# ControlModule.net
KiCad netlist of a schematic drawn in EAGLE
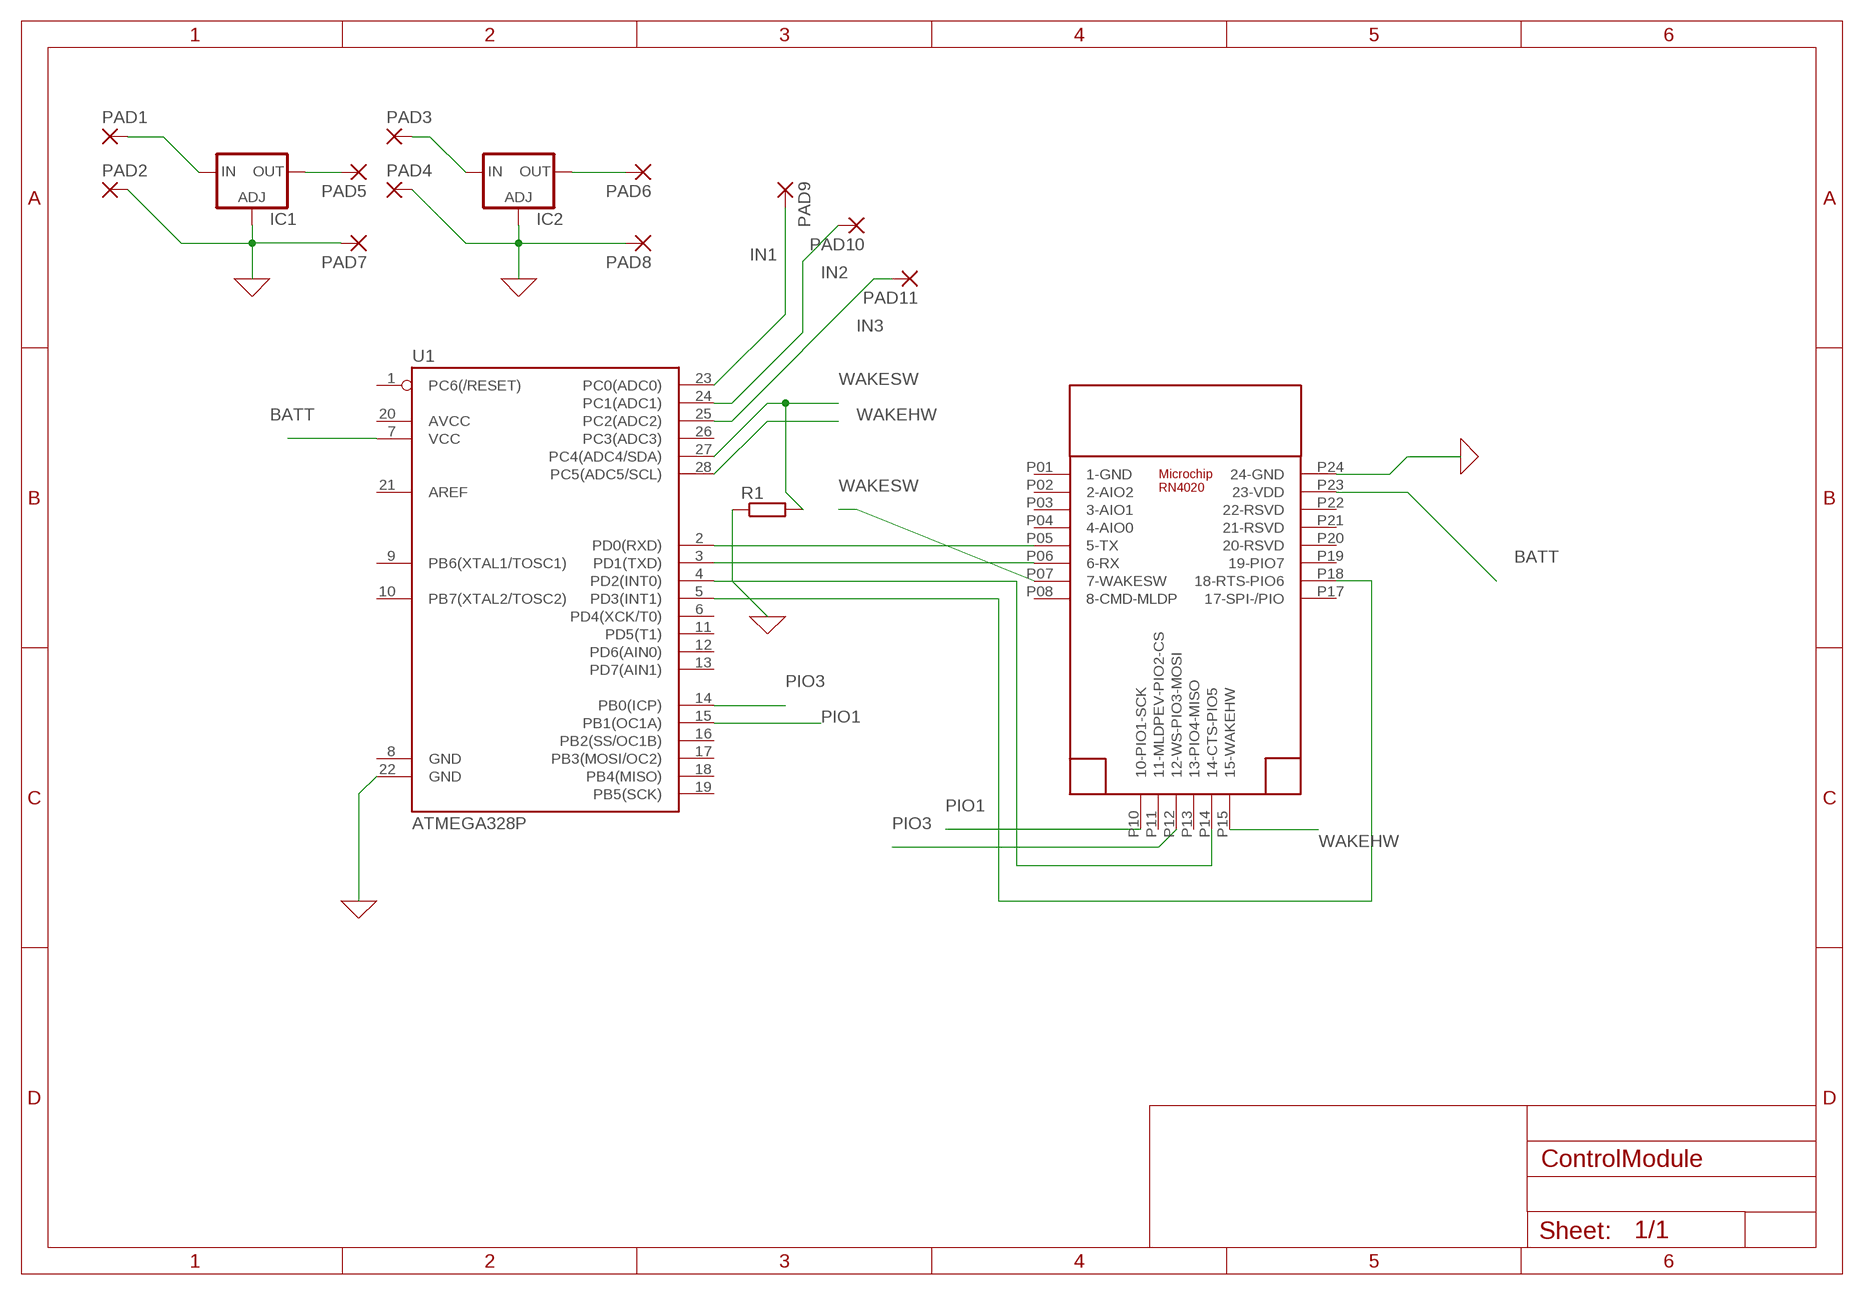
[diagram p0: schematic, sheet 1]

(export (version "E")
  (design (tool "Eeschema 10.0.6"))
  (components
    (comp (ref "IC1")
      (value "LM138-TL")
      (footprint "eagle-import:TO220L1")
      (libsource (lib "eagle-import") (part "LM138-TL"))
    )
    (comp (ref "IC2")
      (value "LM138-TL")
      (footprint "eagle-import:TO220L1")
      (libsource (lib "eagle-import") (part "LM138-TL"))
    )
    (comp (ref "PAD1")
      (value "2,54/1,1")
      (footprint "eagle-import:2,54_1,1")
      (libsource (lib "eagle-import") (part "2,54/1,1"))
    )
    (comp (ref "PAD2")
      (value "2,54/1,1")
      (footprint "eagle-import:2,54_1,1")
      (libsource (lib "eagle-import") (part "2,54/1,1"))
    )
    (comp (ref "PAD3")
      (value "2,54/1,1")
      (footprint "eagle-import:2,54_1,1")
      (libsource (lib "eagle-import") (part "2,54/1,1"))
    )
    (comp (ref "PAD4")
      (value "2,54/1,1")
      (footprint "eagle-import:2,54_1,1")
      (libsource (lib "eagle-import") (part "2,54/1,1"))
    )
    (comp (ref "PAD5")
      (value "2,54/1,1")
      (footprint "eagle-import:2,54_1,1")
      (libsource (lib "eagle-import") (part "2,54/1,1"))
    )
    (comp (ref "PAD6")
      (value "2,54/1,1")
      (footprint "eagle-import:2,54_1,1")
      (libsource (lib "eagle-import") (part "2,54/1,1"))
    )
    (comp (ref "PAD7")
      (value "2,54/1,1")
      (footprint "eagle-import:2,54_1,1")
      (libsource (lib "eagle-import") (part "2,54/1,1"))
    )
    (comp (ref "PAD8")
      (value "2,54/1,1")
      (footprint "eagle-import:2,54_1,1")
      (libsource (lib "eagle-import") (part "2,54/1,1"))
    )
    (comp (ref "PAD9")
      (value "2,54/1,1")
      (footprint "eagle-import:2,54_1,1")
      (libsource (lib "eagle-import") (part "2,54/1,1"))
    )
    (comp (ref "PAD10")
      (value "2,54/1,1")
      (footprint "eagle-import:2,54_1,1")
      (libsource (lib "eagle-import") (part "2,54/1,1"))
    )
    (comp (ref "PAD11")
      (value "2,54/1,1")
      (footprint "eagle-import:2,54_1,1")
      (libsource (lib "eagle-import") (part "2,54/1,1"))
    )
    (comp (ref "R1")
      (value "R-EU_R0805")
      (footprint "eagle-import:R0805")
      (libsource (lib "eagle-import") (part "R-EU_R0805"))
    )
    (comp (ref "U$1")
      (value "RN4020")
      (footprint "eagle-import:RN4020SMD")
      (libsource (lib "eagle-import") (part "RN4020"))
    )
    (comp (ref "U1")
      (value "ATMEGA328P")
      (footprint "eagle-import:DIP28")
      (libsource (lib "eagle-import") (part "ATMEGA328P_PDIP"))
    )
  )
  (nets
    (net (code "1") (name "/BATT") (class "Default")
      (node (ref "U$1") (pin "P23") (pinfunction "23-VDD_P23") (pintype "bidirectional"))
      (node (ref "U1") (pin "7") (pinfunction "VCC_7") (pintype "bidirectional"))
    )
    (net (code "2") (name "/IN1") (class "Default")
      (node (ref "PAD9") (pin "1") (pinfunction "P_1") (pintype "passive"))
      (node (ref "U1") (pin "23") (pinfunction "PC0(ADC0)_23") (pintype "bidirectional"))
    )
    (net (code "3") (name "/IN2") (class "Default")
      (node (ref "PAD10") (pin "1") (pinfunction "P_1") (pintype "passive"))
      (node (ref "U1") (pin "24") (pinfunction "PC1(ADC1)_24") (pintype "bidirectional"))
    )
    (net (code "4") (name "/IN3") (class "Default")
      (node (ref "PAD11") (pin "1") (pinfunction "P_1") (pintype "passive"))
      (node (ref "U1") (pin "25") (pinfunction "PC2(ADC2)_25") (pintype "bidirectional"))
    )
    (net (code "5") (name "/PIO1") (class "Default")
      (node (ref "U$1") (pin "P10") (pinfunction "10-PIO1-SCK_P10") (pintype "bidirectional"))
      (node (ref "U1") (pin "15") (pinfunction "PB1(OC1A)_15") (pintype "bidirectional"))
    )
    (net (code "6") (name "/PIO3") (class "Default")
      (node (ref "U$1") (pin "P12") (pinfunction "12-WS-PIO3-MOSI_P12") (pintype "bidirectional"))
      (node (ref "U1") (pin "14") (pinfunction "PB0(ICP)_14") (pintype "bidirectional"))
    )
    (net (code "7") (name "/WAKEHW") (class "Default")
      (node (ref "U$1") (pin "P15") (pinfunction "15-WAKEHW_P15") (pintype "bidirectional"))
      (node (ref "U1") (pin "28") (pinfunction "PC5(ADC5/SCL)_28") (pintype "bidirectional"))
    )
    (net (code "8") (name "/WAKESW") (class "Default")
      (node (ref "R1") (pin "2") (pinfunction "2_2") (pintype "passive"))
      (node (ref "U$1") (pin "P07") (pinfunction "7-WAKESW_P07") (pintype "bidirectional"))
      (node (ref "U1") (pin "27") (pinfunction "PC4(ADC4/SDA)_27") (pintype "bidirectional"))
    )
    (net (code "9") (name "GND") (class "Default")
      (node (ref "IC1") (pin "1") (pinfunction "ADJ_1") (pintype "input"))
      (node (ref "IC2") (pin "1") (pinfunction "ADJ_1") (pintype "input"))
      (node (ref "PAD2") (pin "1") (pinfunction "P_1") (pintype "passive"))
      (node (ref "PAD4") (pin "1") (pinfunction "P_1") (pintype "passive"))
      (node (ref "PAD7") (pin "1") (pinfunction "P_1") (pintype "passive"))
      (node (ref "PAD8") (pin "1") (pinfunction "P_1") (pintype "passive"))
      (node (ref "R1") (pin "1") (pinfunction "1_1") (pintype "passive"))
      (node (ref "U$1") (pin "P24") (pinfunction "24-GND_P24") (pintype "bidirectional"))
      (node (ref "U1") (pin "22") (pinfunction "GND_22") (pintype "bidirectional"))
    )
    (net (code "10") (name "Net-(IC1-IN)") (class "Default")
      (node (ref "IC1") (pin "3") (pinfunction "IN_3") (pintype "input"))
      (node (ref "PAD1") (pin "1") (pinfunction "P_1") (pintype "passive"))
    )
    (net (code "11") (name "Net-(IC1-OUT)") (class "Default")
      (node (ref "IC1") (pin "2") (pinfunction "OUT_2") (pintype "passive"))
      (node (ref "PAD5") (pin "1") (pinfunction "P_1") (pintype "passive"))
    )
    (net (code "12") (name "Net-(IC2-IN)") (class "Default")
      (node (ref "IC2") (pin "3") (pinfunction "IN_3") (pintype "input"))
      (node (ref "PAD3") (pin "1") (pinfunction "P_1") (pintype "passive"))
    )
    (net (code "13") (name "Net-(IC2-OUT)") (class "Default")
      (node (ref "IC2") (pin "2") (pinfunction "OUT_2") (pintype "passive"))
      (node (ref "PAD6") (pin "1") (pinfunction "P_1") (pintype "passive"))
    )
    (net (code "14") (name "Net-(U$1-5-TX)") (class "Default")
      (node (ref "U$1") (pin "P05") (pinfunction "5-TX_P05") (pintype "bidirectional"))
      (node (ref "U1") (pin "2") (pinfunction "PD0(RXD)_2") (pintype "bidirectional"))
    )
    (net (code "15") (name "Net-(U$1-6-RX)") (class "Default")
      (node (ref "U$1") (pin "P06") (pinfunction "6-RX_P06") (pintype "bidirectional"))
      (node (ref "U1") (pin "3") (pinfunction "PD1(TXD)_3") (pintype "bidirectional"))
    )
    (net (code "16") (name "Net-(U$1-14-CTS-PIO5)") (class "Default")
      (node (ref "U$1") (pin "P14") (pinfunction "14-CTS-PIO5_P14") (pintype "bidirectional"))
      (node (ref "U1") (pin "4") (pinfunction "PD2(INT0)_4") (pintype "bidirectional"))
    )
    (net (code "17") (name "Net-(U$1-18-RTS-PIO6)") (class "Default")
      (node (ref "U$1") (pin "P18") (pinfunction "18-RTS-PIO6_P18") (pintype "bidirectional"))
      (node (ref "U1") (pin "5") (pinfunction "PD3(INT1)_5") (pintype "bidirectional"))
    )
    (net (code "18") (name "unconnected-(U$1-1-GND-PadP01)") (class "Default")
      (node (ref "U$1") (pin "P01") (pinfunction "1-GND_P01") (pintype "bidirectional"))
    )
    (net (code "19") (name "unconnected-(U$1-2-AIO2-PadP02)") (class "Default")
      (node (ref "U$1") (pin "P02") (pinfunction "2-AIO2_P02") (pintype "bidirectional"))
    )
    (net (code "20") (name "unconnected-(U$1-3-AIO1-PadP03)") (class "Default")
      (node (ref "U$1") (pin "P03") (pinfunction "3-AIO1_P03") (pintype "bidirectional"))
    )
    (net (code "21") (name "unconnected-(U$1-4-AIO0-PadP04)") (class "Default")
      (node (ref "U$1") (pin "P04") (pinfunction "4-AIO0_P04") (pintype "bidirectional"))
    )
    (net (code "22") (name "unconnected-(U$1-8-CMD-MLDP-PadP08)") (class "Default")
      (node (ref "U$1") (pin "P08") (pinfunction "8-CMD-MLDP_P08") (pintype "bidirectional"))
    )
    (net (code "23") (name "unconnected-(U$1-11-MLDPEV-PIO2-CS-PadP11)") (class "Default")
      (node (ref "U$1") (pin "P11") (pinfunction "11-MLDPEV-PIO2-CS_P11") (pintype "bidirectional"))
    )
    (net (code "24") (name "unconnected-(U$1-13-PIO4-MISO-PadP13)") (class "Default")
      (node (ref "U$1") (pin "P13") (pinfunction "13-PIO4-MISO_P13") (pintype "bidirectional"))
    )
    (net (code "25") (name "unconnected-(U$1-17-SPI-{slash}PIO-PadP17)") (class "Default")
      (node (ref "U$1") (pin "P17") (pinfunction "17-SPI-/PIO_P17") (pintype "bidirectional"))
    )
    (net (code "26") (name "unconnected-(U$1-19-PIO7-PadP19)") (class "Default")
      (node (ref "U$1") (pin "P19") (pinfunction "19-PIO7_P19") (pintype "bidirectional"))
    )
    (net (code "27") (name "unconnected-(U$1-20-RSVD-PadP20)") (class "Default")
      (node (ref "U$1") (pin "P20") (pinfunction "20-RSVD_P20") (pintype "bidirectional"))
    )
    (net (code "28") (name "unconnected-(U$1-21-RSVD-PadP21)") (class "Default")
      (node (ref "U$1") (pin "P21") (pinfunction "21-RSVD_P21") (pintype "bidirectional"))
    )
    (net (code "29") (name "unconnected-(U$1-22-RSVD-PadP22)") (class "Default")
      (node (ref "U$1") (pin "P22") (pinfunction "22-RSVD_P22") (pintype "bidirectional"))
    )
    (net (code "30") (name "unconnected-(U1-AREF-Pad21)") (class "Default")
      (node (ref "U1") (pin "21") (pinfunction "AREF_21") (pintype "bidirectional"))
    )
    (net (code "31") (name "unconnected-(U1-AVCC-Pad20)") (class "Default")
      (node (ref "U1") (pin "20") (pinfunction "AVCC_20") (pintype "bidirectional"))
    )
    (net (code "32") (name "unconnected-(U1-GND-Pad8)") (class "Default")
      (node (ref "U1") (pin "8") (pinfunction "GND_8") (pintype "bidirectional"))
    )
    (net (code "33") (name "unconnected-(U1-PB2(SS{slash}OC1B)-Pad16)") (class "Default")
      (node (ref "U1") (pin "16") (pinfunction "PB2(SS/OC1B)_16") (pintype "bidirectional"))
    )
    (net (code "34") (name "unconnected-(U1-PB3(MOSI{slash}OC2)-Pad17)") (class "Default")
      (node (ref "U1") (pin "17") (pinfunction "PB3(MOSI/OC2)_17") (pintype "bidirectional"))
    )
    (net (code "35") (name "unconnected-(U1-PB4(MISO)-Pad18)") (class "Default")
      (node (ref "U1") (pin "18") (pinfunction "PB4(MISO)_18") (pintype "bidirectional"))
    )
    (net (code "36") (name "unconnected-(U1-PB5(SCK)-Pad19)") (class "Default")
      (node (ref "U1") (pin "19") (pinfunction "PB5(SCK)_19") (pintype "bidirectional"))
    )
    (net (code "37") (name "unconnected-(U1-PB6(XTAL1{slash}TOSC1)-Pad9)") (class "Default")
      (node (ref "U1") (pin "9") (pinfunction "PB6(XTAL1/TOSC1)_9") (pintype "bidirectional"))
    )
    (net (code "38") (name "unconnected-(U1-PB7(XTAL2{slash}TOSC2)-Pad10)") (class "Default")
      (node (ref "U1") (pin "10") (pinfunction "PB7(XTAL2/TOSC2)_10") (pintype "bidirectional"))
    )
    (net (code "39") (name "unconnected-(U1-PC3(ADC3)-Pad26)") (class "Default")
      (node (ref "U1") (pin "26") (pinfunction "PC3(ADC3)_26") (pintype "bidirectional"))
    )
    (net (code "40") (name "unconnected-(U1-PC6({slash}RESET)-Pad1)") (class "Default")
      (node (ref "U1") (pin "1") (pinfunction "PC6(/RESET)_1") (pintype "bidirectional"))
    )
    (net (code "41") (name "unconnected-(U1-PD4(XCK{slash}T0)-Pad6)") (class "Default")
      (node (ref "U1") (pin "6") (pinfunction "PD4(XCK/T0)_6") (pintype "bidirectional"))
    )
    (net (code "42") (name "unconnected-(U1-PD5(T1)-Pad11)") (class "Default")
      (node (ref "U1") (pin "11") (pinfunction "PD5(T1)_11") (pintype "bidirectional"))
    )
    (net (code "43") (name "unconnected-(U1-PD6(AIN0)-Pad12)") (class "Default")
      (node (ref "U1") (pin "12") (pinfunction "PD6(AIN0)_12") (pintype "bidirectional"))
    )
    (net (code "44") (name "unconnected-(U1-PD7(AIN1)-Pad13)") (class "Default")
      (node (ref "U1") (pin "13") (pinfunction "PD7(AIN1)_13") (pintype "bidirectional"))
    )
  )
)
